# MINI_SAM_D51_r017_b002.net
KiCad netlist of a schematic drawn in EAGLE
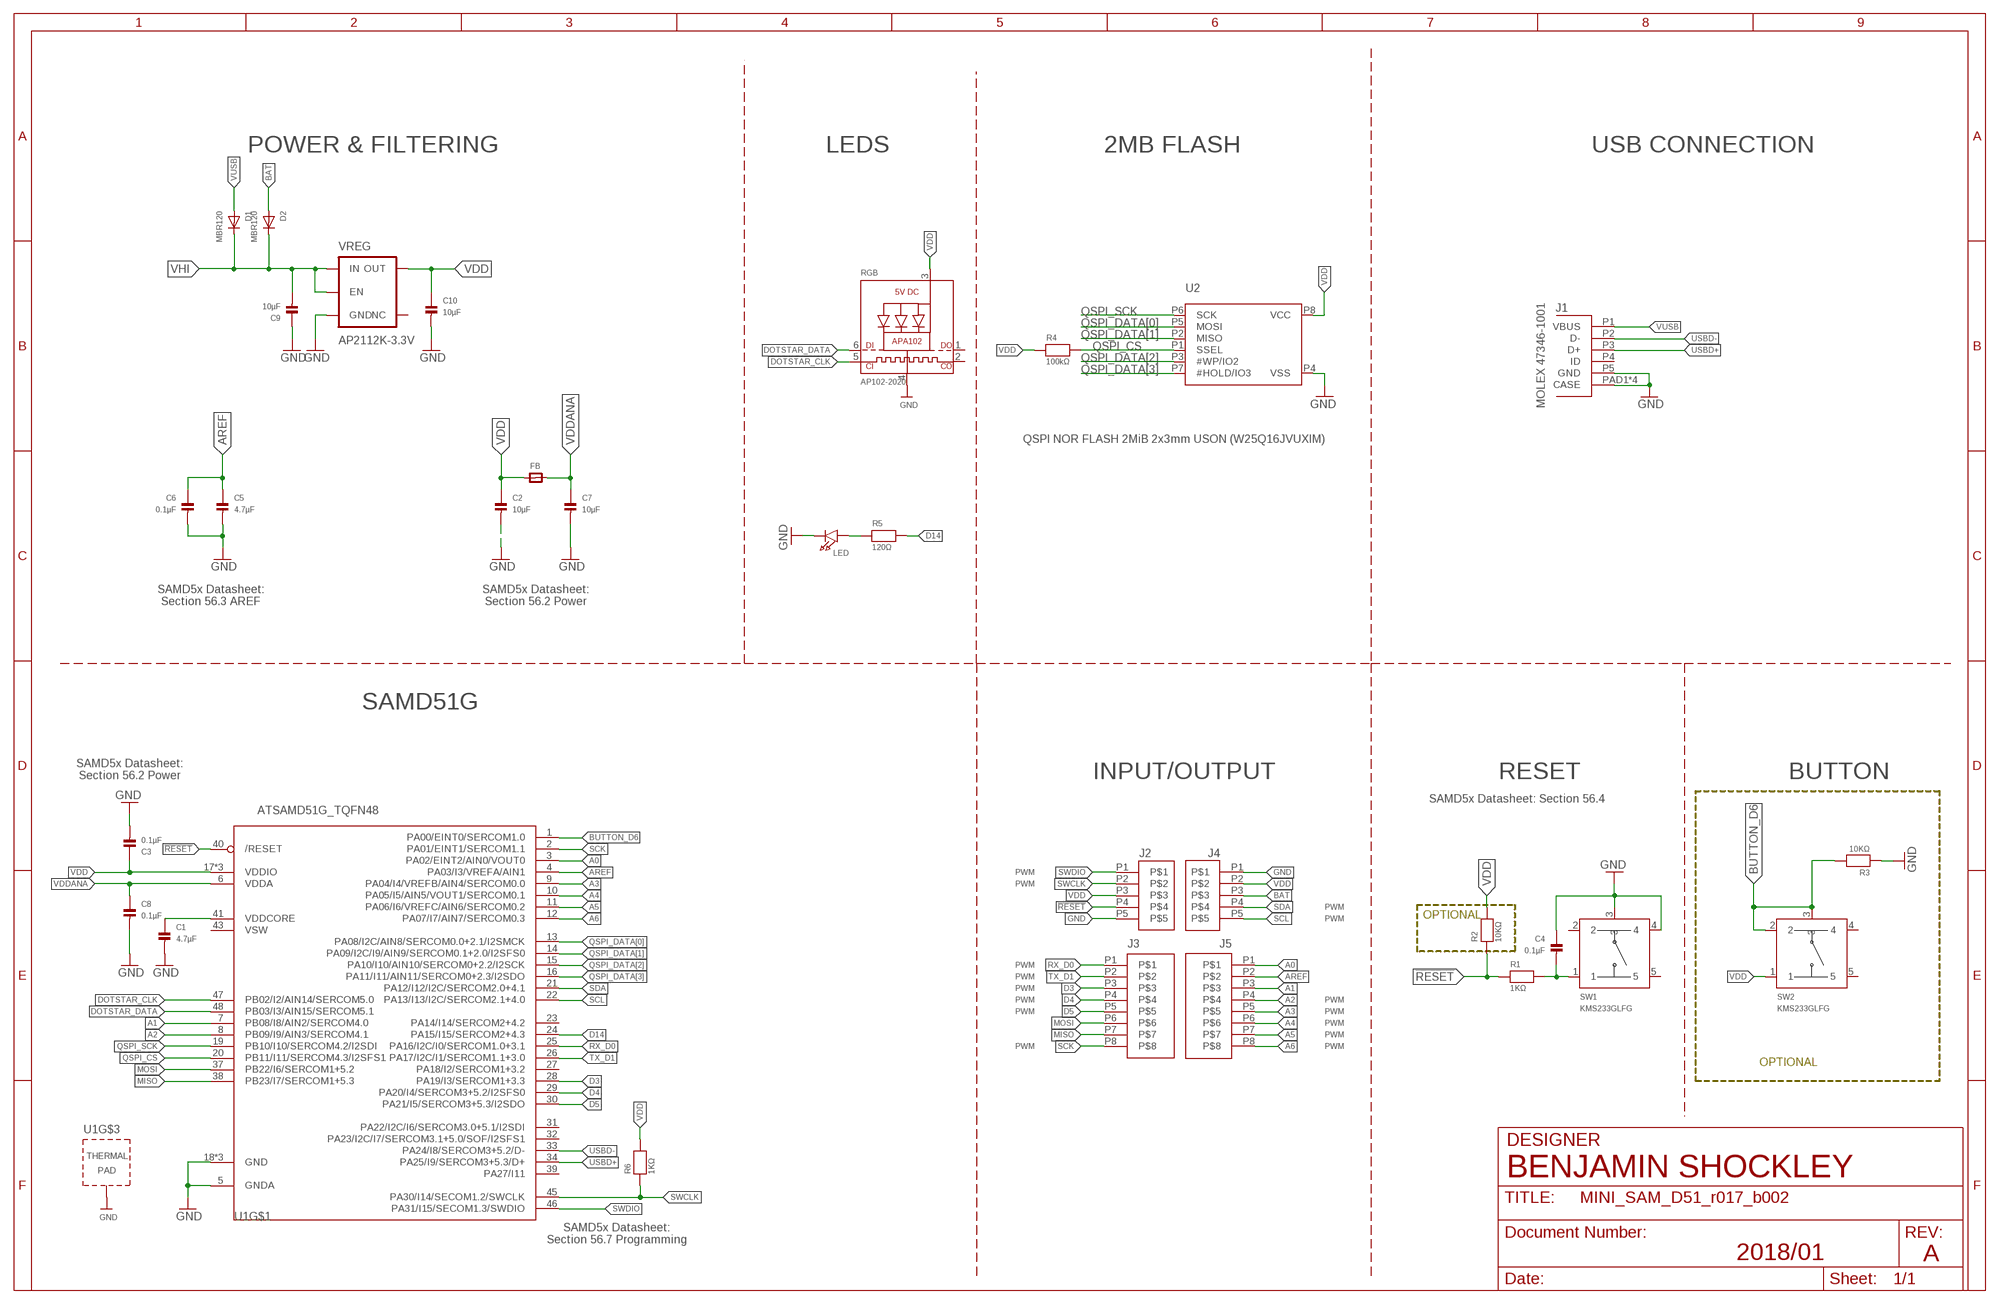
[diagram p0: schematic, sheet 1]

(export (version "E")
  (design (tool "Eeschema 10.0.6"))
  (components
    (comp (ref "C1")
      (value "4.7µF")
      (footprint "eagle-import:_0603MP")
      (libsource (lib "eagle-import") (part "CAP_CERAMIC_0603MP"))
    )
    (comp (ref "C2")
      (value "10µF")
      (footprint "eagle-import:_0603MP")
      (libsource (lib "eagle-import") (part "CAP_CERAMIC_0603MP"))
    )
    (comp (ref "C3")
      (value "0.1µF")
      (footprint "eagle-import:_0603MP")
      (libsource (lib "eagle-import") (part "CAP_CERAMIC_0603MP"))
    )
    (comp (ref "C4")
      (value "0.1µF")
      (footprint "eagle-import:_0603MP")
      (libsource (lib "eagle-import") (part "CAP_CERAMIC_0603MP"))
    )
    (comp (ref "C5")
      (value "4.7µF")
      (footprint "eagle-import:_0603MP")
      (libsource (lib "eagle-import") (part "CAP_CERAMIC_0603MP"))
    )
    (comp (ref "C6")
      (value "0.1µF")
      (footprint "eagle-import:_0603MP")
      (libsource (lib "eagle-import") (part "CAP_CERAMIC_0603MP"))
    )
    (comp (ref "C7")
      (value "10µF")
      (footprint "eagle-import:_0603MP")
      (libsource (lib "eagle-import") (part "CAP_CERAMIC_0603MP"))
    )
    (comp (ref "C8")
      (value "0.1µF")
      (footprint "eagle-import:_0603MP")
      (libsource (lib "eagle-import") (part "CAP_CERAMIC_0603MP"))
    )
    (comp (ref "C9")
      (value "10µF")
      (footprint "eagle-import:_0603MP")
      (libsource (lib "eagle-import") (part "CAP_CERAMIC_0603MP"))
    )
    (comp (ref "C10")
      (value "10µF")
      (footprint "eagle-import:_0603MP")
      (libsource (lib "eagle-import") (part "CAP_CERAMIC_0603MP"))
    )
    (comp (ref "D1")
      (value "MBR120")
      (footprint "eagle-import:SOD-123FL")
      (libsource (lib "eagle-import") (part "DIODE_SOD-123FL"))
    )
    (comp (ref "D2")
      (value "MBR120")
      (footprint "eagle-import:SOD-123FL")
      (libsource (lib "eagle-import") (part "DIODE_SOD-123FL"))
    )
    (comp (ref "FB")
      (value "Impedence: 50 ohm @ 20 MHz, 220 Ohm @ 100 MHz; low DC resistance")
      (footprint "eagle-import:_0603MP")
      (libsource (lib "eagle-import") (part "FERRITE_0603MP"))
    )
    (comp (ref "J1")
      (value "MOLEX_47346-100147346")
      (footprint "eagle-import:MOLEX_47346-1001")
      (libsource (lib "eagle-import") (part "MOLEX_47346-100147346"))
    )
    (comp (ref "J2")
      (value "1X5_HEADER_1.27MMCAST")
      (footprint "eagle-import:1X5_HEADER_1.27MM_CASTELLATED")
      (libsource (lib "eagle-import") (part "1X5_HEADER_1.27MMCAST"))
    )
    (comp (ref "J3")
      (value "1X8_HEADER_1.27MMCAST")
      (footprint "eagle-import:1X8_HEADER_1.27MM_CASTELLATED")
      (libsource (lib "eagle-import") (part "1X8_HEADER_1.27MMCAST"))
    )
    (comp (ref "J4")
      (value "1X5_HEADER_1.27MMCAST")
      (footprint "eagle-import:1X5_HEADER_1.27MM_CASTELLATED")
      (libsource (lib "eagle-import") (part "1X5_HEADER_1.27MMCAST"))
    )
    (comp (ref "J5")
      (value "1X8_HEADER_1.27MMCAST")
      (footprint "eagle-import:1X8_HEADER_1.27MM_CASTELLATED")
      (libsource (lib "eagle-import") (part "1X8_HEADER_1.27MMCAST"))
    )
    (comp (ref "LED")
      (value "VLRK31Q1R2-GS08")
      (footprint "eagle-import:REVERSE_MOUNT_LED")
      (libsource (lib "eagle-import") (part "REVERSEMOUNTLED"))
    )
    (comp (ref "R1")
      (value "1KΩ")
      (footprint "eagle-import:_0603MP")
      (libsource (lib "eagle-import") (part "RESISTOR_0603MP"))
    )
    (comp (ref "R2")
      (value "10KΩ")
      (footprint "eagle-import:_0603MP")
      (libsource (lib "eagle-import") (part "RESISTOR_0603MP"))
    )
    (comp (ref "R3")
      (value "10KΩ")
      (footprint "eagle-import:_0603MP")
      (libsource (lib "eagle-import") (part "RESISTOR_0603MP"))
    )
    (comp (ref "R4")
      (value "100kΩ")
      (footprint "eagle-import:_0603MP")
      (libsource (lib "eagle-import") (part "RESISTOR_0603MP"))
    )
    (comp (ref "R5")
      (value "120Ω")
      (footprint "eagle-import:_0603MP")
      (libsource (lib "eagle-import") (part "RESISTOR_0603MP"))
    )
    (comp (ref "R6")
      (value "1KΩ")
      (footprint "eagle-import:_0603MP")
      (libsource (lib "eagle-import") (part "RESISTOR_0603MP"))
    )
    (comp (ref "RGB")
      (value "AP102-2020")
      (footprint "eagle-import:APA102_2020")
      (libsource (lib "eagle-import") (part "APA1022020"))
    )
    (comp (ref "SW1")
      (value "KMS233GLFG")
      (footprint "eagle-import:KMS_SWITCH")
      (libsource (lib "eagle-import") (part "KMS_SWITCHKMS"))
    )
    (comp (ref "SW2")
      (value "KMS233GLFG")
      (footprint "eagle-import:KMS_SWITCH")
      (libsource (lib "eagle-import") (part "KMS_SWITCHKMS"))
    )
    (comp (ref "U1")
      (value "ATSAMD51G_TQFN48")
      (footprint "eagle-import:TQFN48_7MM")
      (libsource (lib "eagle-import") (part "ATSAMD51G_TQFN48"))
    )
    (comp (ref "U2")
      (value "QSPI NOR FLASH 2MiB 2x3mm USON (W25Q16JVUXIM)")
      (footprint "eagle-import:USON4X3")
      (libsource (lib "eagle-import") (part "SPIFLASH_SOIC8USON4X3"))
    )
    (comp (ref "VREG")
      (value "AP2112K-3.3V")
      (footprint "eagle-import:SOT23-5")
      (libsource (lib "eagle-import") (part "V_REG_AP2112K-3.3V"))
    )
  )
  (nets
    (net (code "1") (name "/VSW") (class "Default")
      (node (ref "U1") (pin "43") (pinfunction "VSW_43") (pintype "power_in"))
    )
    (net (code "2") (name "/~{RESET}") (class "Default")
      (node (ref "J2") (pin "P4") (pinfunction "P$4_P4") (pintype "bidirectional"))
      (node (ref "R1") (pin "1") (pinfunction "1_1") (pintype "passive"))
      (node (ref "R2") (pin "1") (pinfunction "1_1") (pintype "passive"))
      (node (ref "U1") (pin "40") (pinfunction "/RESET_40") (pintype "bidirectional"))
    )
    (net (code "3") (name "A0") (class "Default")
      (node (ref "J5") (pin "P1") (pinfunction "P$1_P1") (pintype "bidirectional"))
      (node (ref "U1") (pin "3") (pinfunction "PA02/EINT2/AIN0/VOUT0_3") (pintype "bidirectional"))
    )
    (net (code "4") (name "A1") (class "Default")
      (node (ref "J5") (pin "P3") (pinfunction "P$3_P3") (pintype "bidirectional"))
      (node (ref "U1") (pin "7") (pinfunction "PB08/I8/AIN2/SERCOM4.0_7") (pintype "bidirectional"))
    )
    (net (code "5") (name "A2") (class "Default")
      (node (ref "J5") (pin "P4") (pinfunction "P$4_P4") (pintype "bidirectional"))
      (node (ref "U1") (pin "8") (pinfunction "PB09/I9/AIN3/SERCOM4.1_8") (pintype "bidirectional"))
    )
    (net (code "6") (name "A3") (class "Default")
      (node (ref "J5") (pin "P5") (pinfunction "P$5_P5") (pintype "bidirectional"))
      (node (ref "U1") (pin "9") (pinfunction "PA04/I4/VREFB/AIN4/SERCOM0.0_9") (pintype "bidirectional"))
    )
    (net (code "7") (name "A4") (class "Default")
      (node (ref "J5") (pin "P6") (pinfunction "P$6_P6") (pintype "bidirectional"))
      (node (ref "U1") (pin "10") (pinfunction "PA05/I5/AIN5/VOUT1/SERCOM0.1_10") (pintype "bidirectional"))
    )
    (net (code "8") (name "A5") (class "Default")
      (node (ref "J5") (pin "P7") (pinfunction "P$7_P7") (pintype "bidirectional"))
      (node (ref "U1") (pin "11") (pinfunction "PA06/I6/VREFC/AIN6/SERCOM0.2_11") (pintype "bidirectional"))
    )
    (net (code "9") (name "A6") (class "Default")
      (node (ref "J5") (pin "P8") (pinfunction "P$8_P8") (pintype "bidirectional"))
      (node (ref "U1") (pin "12") (pinfunction "PA07/I7/AIN7/SERCOM0.3_12") (pintype "bidirectional"))
    )
    (net (code "10") (name "AREF") (class "Default")
      (node (ref "C5") (pin "1") (pinfunction "P$1_1") (pintype "passive"))
      (node (ref "C6") (pin "1") (pinfunction "P$1_1") (pintype "passive"))
      (node (ref "J5") (pin "P2") (pinfunction "P$2_P2") (pintype "bidirectional"))
      (node (ref "U1") (pin "4") (pinfunction "PA03/I3/VREFA/AIN1_4") (pintype "bidirectional"))
    )
    (net (code "11") (name "BAT") (class "Default")
      (node (ref "D2") (pin "A") (pinfunction "A_A") (pintype "passive"))
      (node (ref "J4") (pin "P3") (pinfunction "P$3_P3") (pintype "bidirectional"))
    )
    (net (code "12") (name "BUTTON_D6") (class "Default")
      (node (ref "R3") (pin "2") (pinfunction "2_2") (pintype "passive"))
      (node (ref "SW2") (pin "2") (pinfunction "2_2") (pintype "bidirectional"))
      (node (ref "SW2") (pin "3") (pinfunction "3_3") (pintype "bidirectional"))
      (node (ref "U1") (pin "1") (pinfunction "PA00/EINT0/SERCOM1.0_1") (pintype "bidirectional"))
    )
    (net (code "13") (name "D3") (class "Default")
      (node (ref "J3") (pin "P3") (pinfunction "P$3_P3") (pintype "bidirectional"))
      (node (ref "U1") (pin "28") (pinfunction "PA19/I3/SERCOM1+3.3_28") (pintype "bidirectional"))
    )
    (net (code "14") (name "D4") (class "Default")
      (node (ref "J3") (pin "P4") (pinfunction "P$4_P4") (pintype "bidirectional"))
      (node (ref "U1") (pin "29") (pinfunction "PA20/I4/SERCOM3+5.2/I2SFS0_29") (pintype "bidirectional"))
    )
    (net (code "15") (name "D5") (class "Default")
      (node (ref "J3") (pin "P5") (pinfunction "P$5_P5") (pintype "bidirectional"))
      (node (ref "U1") (pin "30") (pinfunction "PA21/I5/SERCOM3+5.3/I2SDO_30") (pintype "bidirectional"))
    )
    (net (code "16") (name "D14") (class "Default")
      (node (ref "R5") (pin "2") (pinfunction "2_2") (pintype "passive"))
      (node (ref "U1") (pin "24") (pinfunction "PA15/I15/SERCOM2+4.3_24") (pintype "bidirectional"))
    )
    (net (code "17") (name "DOTSTAR_CLK") (class "Default")
      (node (ref "RGB") (pin "5") (pinfunction "CKI_5") (pintype "input"))
      (node (ref "U1") (pin "47") (pinfunction "PB02/I2/AIN14/SERCOM5.0_47") (pintype "bidirectional"))
    )
    (net (code "18") (name "DOTSTAR_DATA") (class "Default")
      (node (ref "RGB") (pin "6") (pinfunction "DI_6") (pintype "input"))
      (node (ref "U1") (pin "48") (pinfunction "PB03/I3/AIN15/SERCOM5.1_48") (pintype "bidirectional"))
    )
    (net (code "19") (name "GND") (class "Default")
      (node (ref "C1") (pin "2") (pinfunction "P$2_2") (pintype "passive"))
      (node (ref "C10") (pin "2") (pinfunction "P$2_2") (pintype "passive"))
      (node (ref "C2") (pin "2") (pinfunction "P$2_2") (pintype "passive"))
      (node (ref "C3") (pin "2") (pinfunction "P$2_2") (pintype "passive"))
      (node (ref "C4") (pin "1") (pinfunction "P$1_1") (pintype "passive"))
      (node (ref "C5") (pin "2") (pinfunction "P$2_2") (pintype "passive"))
      (node (ref "C6") (pin "2") (pinfunction "P$2_2") (pintype "passive"))
      (node (ref "C7") (pin "2") (pinfunction "P$2_2") (pintype "passive"))
      (node (ref "C8") (pin "2") (pinfunction "P$2_2") (pintype "passive"))
      (node (ref "C9") (pin "1") (pinfunction "P$1_1") (pintype "passive"))
      (node (ref "J1") (pin "P5") (pinfunction "GND_P5") (pintype "power_in"))
      (node (ref "J1") (pin "PAD1") (pinfunction "CASE_PAD1") (pintype "bidirectional"))
      (node (ref "J1") (pin "PAD2") (pinfunction "CASE_PAD2") (pintype "bidirectional"))
      (node (ref "J1") (pin "PAD3") (pinfunction "CASE_PAD3") (pintype "bidirectional"))
      (node (ref "J1") (pin "PAD4") (pinfunction "CASE_PAD4") (pintype "bidirectional"))
      (node (ref "J2") (pin "P5") (pinfunction "P$5_P5") (pintype "bidirectional"))
      (node (ref "J4") (pin "P1") (pinfunction "P$1_P1") (pintype "bidirectional"))
      (node (ref "LED") (pin "C") (pinfunction "C_C") (pintype "passive"))
      (node (ref "R3") (pin "1") (pinfunction "1_1") (pintype "passive"))
      (node (ref "RGB") (pin "4") (pinfunction "GND_4") (pintype "power_in"))
      (node (ref "SW1") (pin "3") (pinfunction "3_3") (pintype "bidirectional"))
      (node (ref "SW1") (pin "4") (pinfunction "4_4") (pintype "bidirectional"))
      (node (ref "U1") (pin "18") (pinfunction "GND_18") (pintype "power_in"))
      (node (ref "U1") (pin "35") (pinfunction "GND_35") (pintype "power_in"))
      (node (ref "U1") (pin "42") (pinfunction "GND_42") (pintype "power_in"))
      (node (ref "U1") (pin "5") (pinfunction "GNDA_5") (pintype "power_in"))
      (node (ref "U1") (pin "THERMAL") (pinfunction "TP_THERMAL") (pintype "power_in"))
      (node (ref "U2") (pin "P4") (pinfunction "VSS_P4") (pintype "bidirectional"))
      (node (ref "VREG") (pin "2") (pinfunction "GND_2") (pintype "input"))
    )
    (net (code "20") (name "MISO") (class "Default")
      (node (ref "J3") (pin "P7") (pinfunction "P$7_P7") (pintype "bidirectional"))
      (node (ref "U1") (pin "38") (pinfunction "PB23/I7/SERCOM1+5.3_38") (pintype "bidirectional"))
    )
    (net (code "21") (name "MOSI") (class "Default")
      (node (ref "J3") (pin "P6") (pinfunction "P$6_P6") (pintype "bidirectional"))
      (node (ref "U1") (pin "37") (pinfunction "PB22/I6/SERCOM1+5.2_37") (pintype "bidirectional"))
    )
    (net (code "22") (name "Net-(C1-P$1)") (class "Default")
      (node (ref "C1") (pin "1") (pinfunction "P$1_1") (pintype "passive"))
      (node (ref "U1") (pin "41") (pinfunction "VDDCORE_41") (pintype "power_in"))
    )
    (net (code "23") (name "Net-(C4-P$2)") (class "Default")
      (node (ref "C4") (pin "2") (pinfunction "P$2_2") (pintype "passive"))
      (node (ref "R1") (pin "2") (pinfunction "2_2") (pintype "passive"))
      (node (ref "SW1") (pin "1") (pinfunction "1_1") (pintype "bidirectional"))
    )
    (net (code "24") (name "Net-(LED-PadA)") (class "Default")
      (node (ref "LED") (pin "A") (pinfunction "A_A") (pintype "passive"))
      (node (ref "R5") (pin "1") (pinfunction "1_1") (pintype "passive"))
    )
    (net (code "25") (name "QSPI_CS") (class "Default")
      (node (ref "R4") (pin "2") (pinfunction "2_2") (pintype "passive"))
      (node (ref "U1") (pin "20") (pinfunction "PB11/I11/SERCOM4.3/I2SFS1_20") (pintype "bidirectional"))
      (node (ref "U2") (pin "P1") (pinfunction "SSEL_P1") (pintype "bidirectional"))
    )
    (net (code "26") (name "QSPI_DATA[0]") (class "Default")
      (node (ref "U1") (pin "13") (pinfunction "PA08/I2C/AIN8/SERCOM0.0+2.1/I2SMCK_13") (pintype "bidirectional"))
      (node (ref "U2") (pin "P5") (pinfunction "MOSI_P5") (pintype "bidirectional"))
    )
    (net (code "27") (name "QSPI_DATA[1]") (class "Default")
      (node (ref "U1") (pin "14") (pinfunction "PA09/I2C/I9/AIN9/SERCOM0.1+2.0/I2SFS0_14") (pintype "bidirectional"))
      (node (ref "U2") (pin "P2") (pinfunction "MISO_P2") (pintype "bidirectional"))
    )
    (net (code "28") (name "QSPI_DATA[2]") (class "Default")
      (node (ref "U1") (pin "15") (pinfunction "PA10/I10/AIN10/SERCOM0+2.2/I2SCK_15") (pintype "bidirectional"))
      (node (ref "U2") (pin "P3") (pinfunction "#WP/IO2_P3") (pintype "bidirectional"))
    )
    (net (code "29") (name "QSPI_DATA[3]") (class "Default")
      (node (ref "U1") (pin "16") (pinfunction "PA11/I11/AIN11/SERCOM0+2.3/I2SDO_16") (pintype "bidirectional"))
      (node (ref "U2") (pin "P7") (pinfunction "#HOLD/IO3_P7") (pintype "bidirectional"))
    )
    (net (code "30") (name "QSPI_SCK") (class "Default")
      (node (ref "U1") (pin "19") (pinfunction "PB10/I10/SERCOM4.2/I2SDI_19") (pintype "bidirectional"))
      (node (ref "U2") (pin "P6") (pinfunction "SCK_P6") (pintype "bidirectional"))
    )
    (net (code "31") (name "RX_D0") (class "Default")
      (node (ref "J3") (pin "P1") (pinfunction "P$1_P1") (pintype "bidirectional"))
      (node (ref "U1") (pin "25") (pinfunction "PA16/I2C/I0/SERCOM1.0+3.1_25") (pintype "bidirectional"))
    )
    (net (code "32") (name "SCK") (class "Default")
      (node (ref "J3") (pin "P8") (pinfunction "P$8_P8") (pintype "bidirectional"))
      (node (ref "U1") (pin "2") (pinfunction "PA01/EINT1/SERCOM1.1_2") (pintype "bidirectional"))
    )
    (net (code "33") (name "SCL") (class "Default")
      (node (ref "J4") (pin "P5") (pinfunction "P$5_P5") (pintype "bidirectional"))
      (node (ref "U1") (pin "22") (pinfunction "PA13/I13/I2C/SERCOM2.1+4.0_22") (pintype "bidirectional"))
    )
    (net (code "34") (name "SDA") (class "Default")
      (node (ref "J4") (pin "P4") (pinfunction "P$4_P4") (pintype "bidirectional"))
      (node (ref "U1") (pin "21") (pinfunction "PA12/I12/I2C/SERCOM2.0+4.1_21") (pintype "bidirectional"))
    )
    (net (code "35") (name "SWCLK") (class "Default")
      (node (ref "J2") (pin "P2") (pinfunction "P$2_P2") (pintype "bidirectional"))
      (node (ref "R6") (pin "1") (pinfunction "1_1") (pintype "passive"))
      (node (ref "U1") (pin "45") (pinfunction "PA30/I14/SECOM1.2/SWCLK_45") (pintype "bidirectional"))
    )
    (net (code "36") (name "SWDIO") (class "Default")
      (node (ref "J2") (pin "P1") (pinfunction "P$1_P1") (pintype "bidirectional"))
      (node (ref "U1") (pin "46") (pinfunction "PA31/I15/SECOM1.3/SWDIO_46") (pintype "bidirectional"))
    )
    (net (code "37") (name "TX_D1") (class "Default")
      (node (ref "J3") (pin "P2") (pinfunction "P$2_P2") (pintype "bidirectional"))
      (node (ref "U1") (pin "26") (pinfunction "PA17/I2C/I1/SERCOM1.1+3.0_26") (pintype "bidirectional"))
    )
    (net (code "38") (name "USBD+") (class "Default")
      (node (ref "J1") (pin "P3") (pinfunction "D+_P3") (pintype "bidirectional"))
      (node (ref "U1") (pin "34") (pinfunction "PA25/I9/SERCOM3+5.3/D+_34") (pintype "bidirectional"))
    )
    (net (code "39") (name "USBD-") (class "Default")
      (node (ref "J1") (pin "P2") (pinfunction "D-_P2") (pintype "bidirectional"))
      (node (ref "U1") (pin "33") (pinfunction "PA24/I8/SERCOM3+5.2/D-_33") (pintype "bidirectional"))
    )
    (net (code "40") (name "VDD") (class "Default")
      (node (ref "C10") (pin "1") (pinfunction "P$1_1") (pintype "passive"))
      (node (ref "C2") (pin "1") (pinfunction "P$1_1") (pintype "passive"))
      (node (ref "C3") (pin "1") (pinfunction "P$1_1") (pintype "passive"))
      (node (ref "FB") (pin "1") (pinfunction "P$1_1") (pintype "passive"))
      (node (ref "J2") (pin "P3") (pinfunction "P$3_P3") (pintype "bidirectional"))
      (node (ref "J4") (pin "P2") (pinfunction "P$2_P2") (pintype "bidirectional"))
      (node (ref "R2") (pin "2") (pinfunction "2_2") (pintype "passive"))
      (node (ref "R4") (pin "1") (pinfunction "1_1") (pintype "passive"))
      (node (ref "R6") (pin "2") (pinfunction "2_2") (pintype "passive"))
      (node (ref "RGB") (pin "3") (pinfunction "VDD_3") (pintype "power_in"))
      (node (ref "SW2") (pin "1") (pinfunction "1_1") (pintype "bidirectional"))
      (node (ref "U1") (pin "17") (pinfunction "VDDIO_17") (pintype "power_in"))
      (node (ref "U1") (pin "36") (pinfunction "VDDIO_36") (pintype "power_in"))
      (node (ref "U1") (pin "44") (pinfunction "VDDIO_44") (pintype "power_in"))
      (node (ref "U2") (pin "P8") (pinfunction "VCC_P8") (pintype "bidirectional"))
      (node (ref "VREG") (pin "5") (pinfunction "OUT_5") (pintype "passive"))
    )
    (net (code "41") (name "VDDANA") (class "Default")
      (node (ref "C7") (pin "1") (pinfunction "P$1_1") (pintype "passive"))
      (node (ref "C8") (pin "1") (pinfunction "P$1_1") (pintype "passive"))
      (node (ref "FB") (pin "2") (pinfunction "P$2_2") (pintype "passive"))
      (node (ref "U1") (pin "6") (pinfunction "VDDA_6") (pintype "power_in"))
    )
    (net (code "42") (name "VHI") (class "Default")
      (node (ref "C9") (pin "2") (pinfunction "P$2_2") (pintype "passive"))
      (node (ref "D1") (pin "C") (pinfunction "C_C") (pintype "passive"))
      (node (ref "D2") (pin "C") (pinfunction "C_C") (pintype "passive"))
      (node (ref "VREG") (pin "1") (pinfunction "IN_1") (pintype "input"))
      (node (ref "VREG") (pin "3") (pinfunction "EN_3") (pintype "input"))
    )
    (net (code "43") (name "VUSB") (class "Default")
      (node (ref "D1") (pin "A") (pinfunction "A_A") (pintype "passive"))
      (node (ref "J1") (pin "P1") (pinfunction "VBUS_P1") (pintype "power_in"))
    )
    (net (code "44") (name "unconnected-(J1-ID-PadP4)") (class "Default")
      (node (ref "J1") (pin "P4") (pinfunction "ID_P4") (pintype "bidirectional"))
    )
    (net (code "45") (name "unconnected-(RGB-CKO-Pad2)") (class "Default")
      (node (ref "RGB") (pin "2") (pinfunction "CKO_2") (pintype "output"))
    )
    (net (code "46") (name "unconnected-(RGB-DO-Pad1)") (class "Default")
      (node (ref "RGB") (pin "1") (pinfunction "DO_1") (pintype "output"))
    )
    (net (code "47") (name "unconnected-(SW1-Pad2)") (class "Default")
      (node (ref "SW1") (pin "2") (pinfunction "2_2") (pintype "bidirectional"))
    )
    (net (code "48") (name "unconnected-(SW1-Pad5)") (class "Default")
      (node (ref "SW1") (pin "5") (pinfunction "5_5") (pintype "bidirectional"))
    )
    (net (code "49") (name "unconnected-(SW2-Pad4)") (class "Default")
      (node (ref "SW2") (pin "4") (pinfunction "4_4") (pintype "bidirectional"))
    )
    (net (code "50") (name "unconnected-(SW2-Pad5)") (class "Default")
      (node (ref "SW2") (pin "5") (pinfunction "5_5") (pintype "bidirectional"))
    )
    (net (code "51") (name "unconnected-(U1A-PA14{slash}I14{slash}SERCOM2+4.2-Pad23)") (class "Default")
      (node (ref "U1") (pin "23") (pinfunction "PA14/I14/SERCOM2+4.2_23") (pintype "bidirectional"))
    )
    (net (code "52") (name "unconnected-(U1A-PA18{slash}I2{slash}SERCOM1+3.2-Pad27)") (class "Default")
      (node (ref "U1") (pin "27") (pinfunction "PA18/I2/SERCOM1+3.2_27") (pintype "bidirectional"))
    )
    (net (code "53") (name "unconnected-(U1A-PA22{slash}I2C{slash}I6{slash}SERCOM3.0+5.1{slash}I2SDI-Pad31)") (class "Default")
      (node (ref "U1") (pin "31") (pinfunction "PA22/I2C/I6/SERCOM3.0+5.1/I2SDI_31") (pintype "bidirectional"))
    )
    (net (code "54") (name "unconnected-(U1A-PA23{slash}I2C{slash}I7{slash}SERCOM3.1+5.0{slash}SOF{slash}I2SFS1-Pad32)") (class "Default")
      (node (ref "U1") (pin "32") (pinfunction "PA23/I2C/I7/SERCOM3.1+5.0/SOF/I2SFS1_32") (pintype "bidirectional"))
    )
    (net (code "55") (name "unconnected-(U1A-PA27{slash}I11-Pad39)") (class "Default")
      (node (ref "U1") (pin "39") (pinfunction "PA27/I11_39") (pintype "bidirectional"))
    )
    (net (code "56") (name "unconnected-(VREG-NC-Pad4)") (class "Default")
      (node (ref "VREG") (pin "4") (pinfunction "NC_4") (pintype "input"))
    )
  )
)
